# 74hc595.net
KiCad netlist of a schematic drawn in Altium Designer
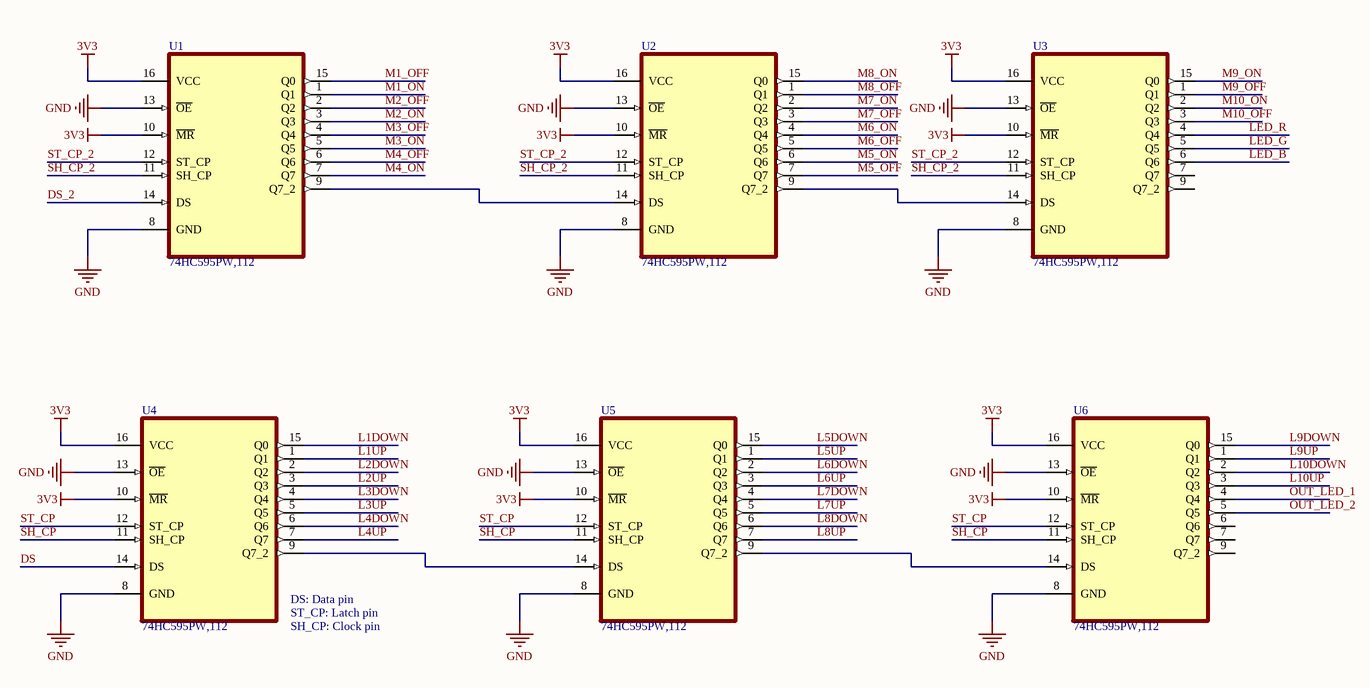
[diagram p0: 74hc595.SchDoc]

(export (version "E")
  (design (tool "Eeschema 10.0.6"))
  (components
    (comp (ref "U1")
      (value "74HC595PW,112")
      (footprint "SOP65P640X110-16N:SOP65P640X110-16N")
      (description "Shift Shift Register 1 Element 8 Bit 16-TSSOP")
      (fields (field (name "MF") "Nexperia"))
      (libsource (lib "74HC595PW,112") (part "74HC595PW,112"))
    )
    (comp (ref "U2")
      (value "74HC595PW,112")
      (footprint "SOP65P640X110-16N:SOP65P640X110-16N")
      (description "Shift Shift Register 1 Element 8 Bit 16-TSSOP")
      (fields (field (name "MF") "Nexperia"))
      (libsource (lib "74HC595PW,112") (part "74HC595PW,112"))
    )
    (comp (ref "U3")
      (value "74HC595PW,112")
      (footprint "SOP65P640X110-16N:SOP65P640X110-16N")
      (description "Shift Shift Register 1 Element 8 Bit 16-TSSOP")
      (fields (field (name "MF") "Nexperia"))
      (libsource (lib "74HC595PW,112") (part "74HC595PW,112"))
    )
    (comp (ref "U4")
      (value "74HC595PW,112")
      (footprint "SOP65P640X110-16N:SOP65P640X110-16N")
      (description "Shift Shift Register 1 Element 8 Bit 16-TSSOP")
      (fields (field (name "MF") "Nexperia"))
      (libsource (lib "74HC595PW,112") (part "74HC595PW,112"))
    )
    (comp (ref "U5")
      (value "74HC595PW,112")
      (footprint "SOP65P640X110-16N:SOP65P640X110-16N")
      (description "Shift Shift Register 1 Element 8 Bit 16-TSSOP")
      (fields (field (name "MF") "Nexperia"))
      (libsource (lib "74HC595PW,112") (part "74HC595PW,112"))
    )
    (comp (ref "U6")
      (value "74HC595PW,112")
      (footprint "SOP65P640X110-16N:SOP65P640X110-16N")
      (description "Shift Shift Register 1 Element 8 Bit 16-TSSOP")
      (fields (field (name "MF") "Nexperia"))
      (libsource (lib "74HC595PW,112") (part "74HC595PW,112"))
    )
  )
  (nets
    (net (code "1") (name "/DS") (class "Default")
      (node (ref "U4") (pin "14") (pinfunction "DS_14") (pintype "input"))
    )
    (net (code "2") (name "/DS_2") (class "Default")
      (node (ref "U1") (pin "14") (pinfunction "DS_14") (pintype "input"))
    )
    (net (code "3") (name "/L1DOWN") (class "Default")
      (node (ref "U4") (pin "15") (pinfunction "Q0_15") (pintype "output"))
    )
    (net (code "4") (name "/L1UP") (class "Default")
      (node (ref "U4") (pin "1") (pinfunction "Q1_1") (pintype "output"))
    )
    (net (code "5") (name "/L2DOWN") (class "Default")
      (node (ref "U4") (pin "2") (pinfunction "Q2_2") (pintype "output"))
    )
    (net (code "6") (name "/L2UP") (class "Default")
      (node (ref "U4") (pin "3") (pinfunction "Q3_3") (pintype "output"))
    )
    (net (code "7") (name "/L3DOWN") (class "Default")
      (node (ref "U4") (pin "4") (pinfunction "Q4_4") (pintype "output"))
    )
    (net (code "8") (name "/L3UP") (class "Default")
      (node (ref "U4") (pin "5") (pinfunction "Q5_5") (pintype "output"))
    )
    (net (code "9") (name "/L4DOWN") (class "Default")
      (node (ref "U4") (pin "6") (pinfunction "Q6_6") (pintype "output"))
    )
    (net (code "10") (name "/L4UP") (class "Default")
      (node (ref "U4") (pin "7") (pinfunction "Q7_7") (pintype "output"))
    )
    (net (code "11") (name "/L5DOWN") (class "Default")
      (node (ref "U5") (pin "15") (pinfunction "Q0_15") (pintype "output"))
    )
    (net (code "12") (name "/L5UP") (class "Default")
      (node (ref "U5") (pin "1") (pinfunction "Q1_1") (pintype "output"))
    )
    (net (code "13") (name "/L6DOWN") (class "Default")
      (node (ref "U5") (pin "2") (pinfunction "Q2_2") (pintype "output"))
    )
    (net (code "14") (name "/L6UP") (class "Default")
      (node (ref "U5") (pin "3") (pinfunction "Q3_3") (pintype "output"))
    )
    (net (code "15") (name "/L7DOWN") (class "Default")
      (node (ref "U5") (pin "4") (pinfunction "Q4_4") (pintype "output"))
    )
    (net (code "16") (name "/L7UP") (class "Default")
      (node (ref "U5") (pin "5") (pinfunction "Q5_5") (pintype "output"))
    )
    (net (code "17") (name "/L8DOWN") (class "Default")
      (node (ref "U5") (pin "6") (pinfunction "Q6_6") (pintype "output"))
    )
    (net (code "18") (name "/L8UP") (class "Default")
      (node (ref "U5") (pin "7") (pinfunction "Q7_7") (pintype "output"))
    )
    (net (code "19") (name "/L9DOWN") (class "Default")
      (node (ref "U6") (pin "15") (pinfunction "Q0_15") (pintype "output"))
    )
    (net (code "20") (name "/L9UP") (class "Default")
      (node (ref "U6") (pin "1") (pinfunction "Q1_1") (pintype "output"))
    )
    (net (code "21") (name "/L10DOWN") (class "Default")
      (node (ref "U6") (pin "2") (pinfunction "Q2_2") (pintype "output"))
    )
    (net (code "22") (name "/L10UP") (class "Default")
      (node (ref "U6") (pin "3") (pinfunction "Q3_3") (pintype "output"))
    )
    (net (code "23") (name "/LED_B") (class "Default")
      (node (ref "U3") (pin "6") (pinfunction "Q6_6") (pintype "output"))
    )
    (net (code "24") (name "/LED_G") (class "Default")
      (node (ref "U3") (pin "5") (pinfunction "Q5_5") (pintype "output"))
    )
    (net (code "25") (name "/LED_R") (class "Default")
      (node (ref "U3") (pin "4") (pinfunction "Q4_4") (pintype "output"))
    )
    (net (code "26") (name "/M1_OFF") (class "Default")
      (node (ref "U1") (pin "15") (pinfunction "Q0_15") (pintype "output"))
    )
    (net (code "27") (name "/M1_ON") (class "Default")
      (node (ref "U1") (pin "1") (pinfunction "Q1_1") (pintype "output"))
    )
    (net (code "28") (name "/M2_OFF") (class "Default")
      (node (ref "U1") (pin "2") (pinfunction "Q2_2") (pintype "output"))
    )
    (net (code "29") (name "/M2_ON") (class "Default")
      (node (ref "U1") (pin "3") (pinfunction "Q3_3") (pintype "output"))
    )
    (net (code "30") (name "/M3_OFF") (class "Default")
      (node (ref "U1") (pin "4") (pinfunction "Q4_4") (pintype "output"))
    )
    (net (code "31") (name "/M3_ON") (class "Default")
      (node (ref "U1") (pin "5") (pinfunction "Q5_5") (pintype "output"))
    )
    (net (code "32") (name "/M4_OFF") (class "Default")
      (node (ref "U1") (pin "6") (pinfunction "Q6_6") (pintype "output"))
    )
    (net (code "33") (name "/M4_ON") (class "Default")
      (node (ref "U1") (pin "7") (pinfunction "Q7_7") (pintype "output"))
    )
    (net (code "34") (name "/M5_OFF") (class "Default")
      (node (ref "U2") (pin "7") (pinfunction "Q7_7") (pintype "output"))
    )
    (net (code "35") (name "/M5_ON") (class "Default")
      (node (ref "U2") (pin "6") (pinfunction "Q6_6") (pintype "output"))
    )
    (net (code "36") (name "/M6_OFF") (class "Default")
      (node (ref "U2") (pin "5") (pinfunction "Q5_5") (pintype "output"))
    )
    (net (code "37") (name "/M6_ON") (class "Default")
      (node (ref "U2") (pin "4") (pinfunction "Q4_4") (pintype "output"))
    )
    (net (code "38") (name "/M7_OFF") (class "Default")
      (node (ref "U2") (pin "3") (pinfunction "Q3_3") (pintype "output"))
    )
    (net (code "39") (name "/M7_ON") (class "Default")
      (node (ref "U2") (pin "2") (pinfunction "Q2_2") (pintype "output"))
    )
    (net (code "40") (name "/M8_OFF") (class "Default")
      (node (ref "U2") (pin "1") (pinfunction "Q1_1") (pintype "output"))
    )
    (net (code "41") (name "/M8_ON") (class "Default")
      (node (ref "U2") (pin "15") (pinfunction "Q0_15") (pintype "output"))
    )
    (net (code "42") (name "/M9_OFF") (class "Default")
      (node (ref "U3") (pin "1") (pinfunction "Q1_1") (pintype "output"))
    )
    (net (code "43") (name "/M9_ON") (class "Default")
      (node (ref "U3") (pin "15") (pinfunction "Q0_15") (pintype "output"))
    )
    (net (code "44") (name "/M10_OFF") (class "Default")
      (node (ref "U3") (pin "3") (pinfunction "Q3_3") (pintype "output"))
    )
    (net (code "45") (name "/M10_ON") (class "Default")
      (node (ref "U3") (pin "2") (pinfunction "Q2_2") (pintype "output"))
    )
    (net (code "46") (name "/OUT_LED_1") (class "Default")
      (node (ref "U6") (pin "4") (pinfunction "Q4_4") (pintype "output"))
    )
    (net (code "47") (name "/OUT_LED_2") (class "Default")
      (node (ref "U6") (pin "5") (pinfunction "Q5_5") (pintype "output"))
    )
    (net (code "48") (name "/SH_CP") (class "Default")
      (node (ref "U4") (pin "11") (pinfunction "SH_CP_11") (pintype "input"))
      (node (ref "U5") (pin "11") (pinfunction "SH_CP_11") (pintype "input"))
      (node (ref "U6") (pin "11") (pinfunction "SH_CP_11") (pintype "input"))
    )
    (net (code "49") (name "/SH_CP_2") (class "Default")
      (node (ref "U1") (pin "11") (pinfunction "SH_CP_11") (pintype "input"))
      (node (ref "U2") (pin "11") (pinfunction "SH_CP_11") (pintype "input"))
      (node (ref "U3") (pin "11") (pinfunction "SH_CP_11") (pintype "input"))
    )
    (net (code "50") (name "/ST_CP") (class "Default")
      (node (ref "U4") (pin "12") (pinfunction "ST_CP_12") (pintype "input"))
      (node (ref "U5") (pin "12") (pinfunction "ST_CP_12") (pintype "input"))
      (node (ref "U6") (pin "12") (pinfunction "ST_CP_12") (pintype "input"))
    )
    (net (code "51") (name "/ST_CP_2") (class "Default")
      (node (ref "U1") (pin "12") (pinfunction "ST_CP_12") (pintype "input"))
      (node (ref "U2") (pin "12") (pinfunction "ST_CP_12") (pintype "input"))
      (node (ref "U3") (pin "12") (pinfunction "ST_CP_12") (pintype "input"))
    )
    (net (code "52") (name "3V3") (class "Default")
      (node (ref "U1") (pin "10") (pinfunction "~{MR}_10") (pintype "input"))
      (node (ref "U1") (pin "16") (pinfunction "VCC_16") (pintype "power_in"))
      (node (ref "U2") (pin "10") (pinfunction "~{MR}_10") (pintype "input"))
      (node (ref "U2") (pin "16") (pinfunction "VCC_16") (pintype "power_in"))
      (node (ref "U3") (pin "10") (pinfunction "~{MR}_10") (pintype "input"))
      (node (ref "U3") (pin "16") (pinfunction "VCC_16") (pintype "power_in"))
      (node (ref "U4") (pin "10") (pinfunction "~{MR}_10") (pintype "input"))
      (node (ref "U4") (pin "16") (pinfunction "VCC_16") (pintype "power_in"))
      (node (ref "U5") (pin "10") (pinfunction "~{MR}_10") (pintype "input"))
      (node (ref "U5") (pin "16") (pinfunction "VCC_16") (pintype "power_in"))
      (node (ref "U6") (pin "10") (pinfunction "~{MR}_10") (pintype "input"))
      (node (ref "U6") (pin "16") (pinfunction "VCC_16") (pintype "power_in"))
    )
    (net (code "53") (name "GND") (class "Default")
      (node (ref "U1") (pin "13") (pinfunction "~{OE}_13") (pintype "input"))
      (node (ref "U1") (pin "8") (pinfunction "GND_8") (pintype "passive"))
      (node (ref "U2") (pin "13") (pinfunction "~{OE}_13") (pintype "input"))
      (node (ref "U2") (pin "8") (pinfunction "GND_8") (pintype "passive"))
      (node (ref "U3") (pin "13") (pinfunction "~{OE}_13") (pintype "input"))
      (node (ref "U3") (pin "8") (pinfunction "GND_8") (pintype "passive"))
      (node (ref "U4") (pin "13") (pinfunction "~{OE}_13") (pintype "input"))
      (node (ref "U4") (pin "8") (pinfunction "GND_8") (pintype "passive"))
      (node (ref "U5") (pin "13") (pinfunction "~{OE}_13") (pintype "input"))
      (node (ref "U5") (pin "8") (pinfunction "GND_8") (pintype "passive"))
      (node (ref "U6") (pin "13") (pinfunction "~{OE}_13") (pintype "input"))
      (node (ref "U6") (pin "8") (pinfunction "GND_8") (pintype "passive"))
    )
    (net (code "54") (name "Net-(U1-Q7_2)") (class "Default")
      (node (ref "U1") (pin "9") (pinfunction "Q7_2_9") (pintype "output"))
      (node (ref "U2") (pin "14") (pinfunction "DS_14") (pintype "input"))
    )
    (net (code "55") (name "Net-(U2-Q7_2)") (class "Default")
      (node (ref "U2") (pin "9") (pinfunction "Q7_2_9") (pintype "output"))
      (node (ref "U3") (pin "14") (pinfunction "DS_14") (pintype "input"))
    )
    (net (code "56") (name "Net-(U4-Q7_2)") (class "Default")
      (node (ref "U4") (pin "9") (pinfunction "Q7_2_9") (pintype "output"))
      (node (ref "U5") (pin "14") (pinfunction "DS_14") (pintype "input"))
    )
    (net (code "57") (name "Net-(U5-Q7_2)") (class "Default")
      (node (ref "U5") (pin "9") (pinfunction "Q7_2_9") (pintype "output"))
      (node (ref "U6") (pin "14") (pinfunction "DS_14") (pintype "input"))
    )
    (net (code "58") (name "unconnected-(U3-Q7-Pad7)") (class "Default")
      (node (ref "U3") (pin "7") (pinfunction "Q7_7") (pintype "output"))
    )
    (net (code "59") (name "unconnected-(U3-Q7_2-Pad9)") (class "Default")
      (node (ref "U3") (pin "9") (pinfunction "Q7_2_9") (pintype "output"))
    )
    (net (code "60") (name "unconnected-(U6-Q6-Pad6)") (class "Default")
      (node (ref "U6") (pin "6") (pinfunction "Q6_6") (pintype "output"))
    )
    (net (code "61") (name "unconnected-(U6-Q7-Pad7)") (class "Default")
      (node (ref "U6") (pin "7") (pinfunction "Q7_7") (pintype "output"))
    )
    (net (code "62") (name "unconnected-(U6-Q7_2-Pad9)") (class "Default")
      (node (ref "U6") (pin "9") (pinfunction "Q7_2_9") (pintype "output"))
    )
  )
)
